# microcontroller.net
KiCad netlist of a schematic drawn in Altium Designer
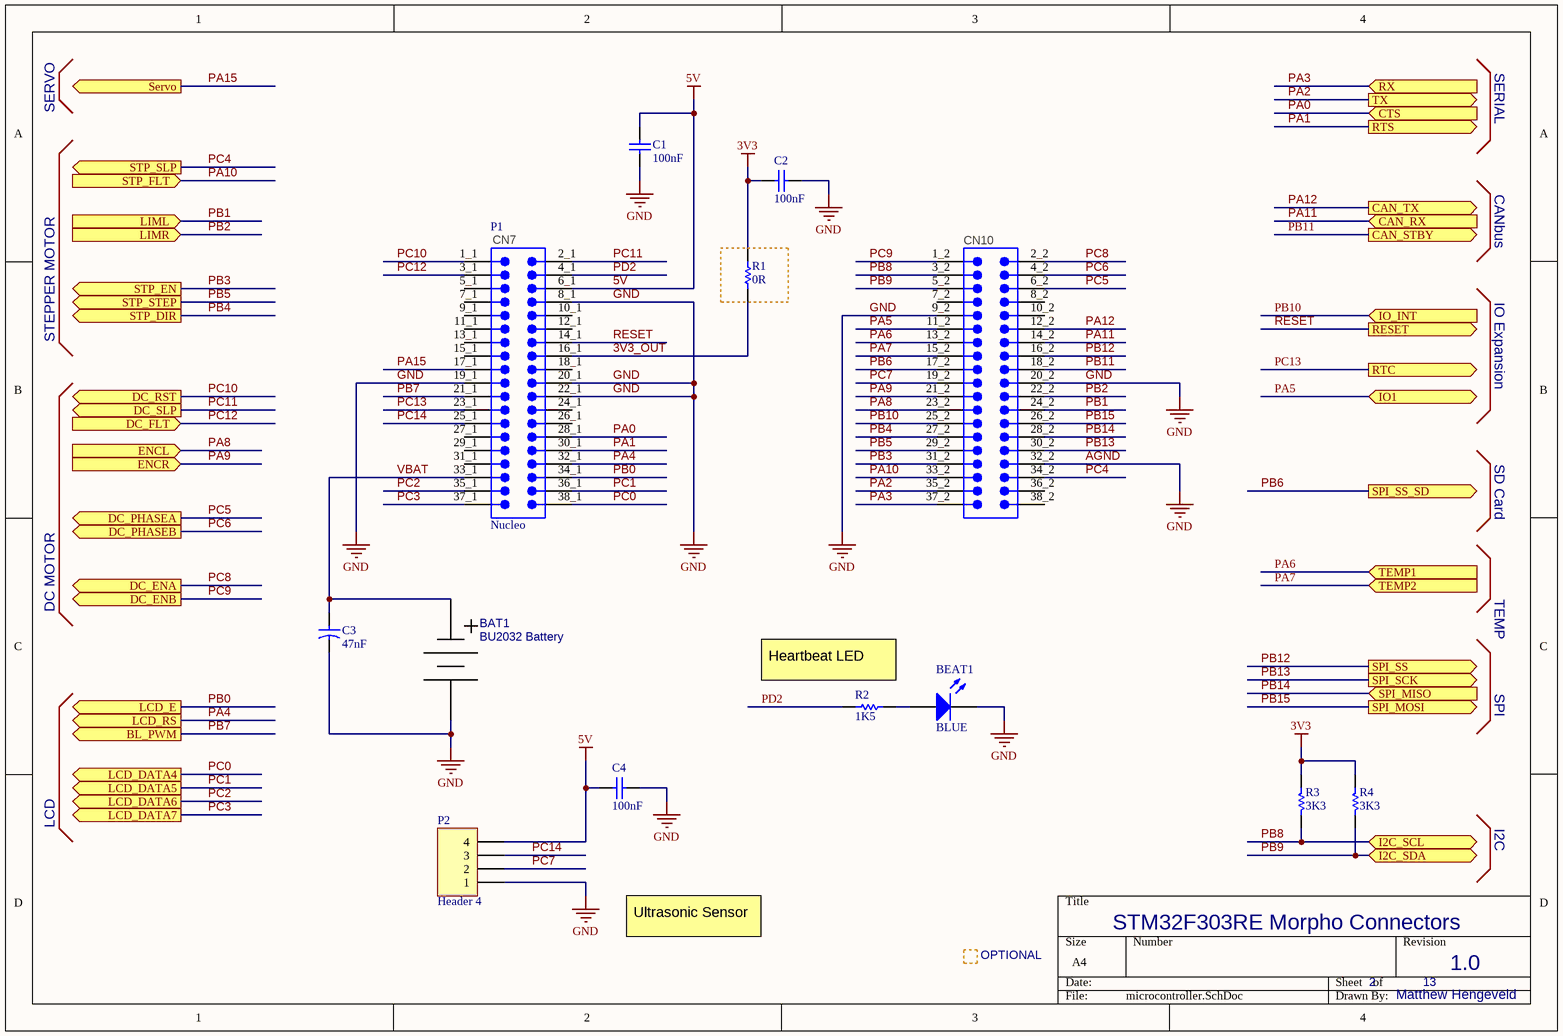
[diagram p0: microcontroller.SchDoc]

(export (version "E")
  (design (tool "Eeschema 10.0.6"))
  (components
    (comp (ref "BAT1")
      (value "BU2032 Battery")
      (footprint "BU2032")
      (libsource (lib "Hengeveld") (part "BU2032 Battery"))
    )
    (comp (ref "BEAT1")
      (value "BLUE")
      (footprint "0805_A")
      (description "SMD mono-color Chip LED, WL-SMCW, Red")
      (fields (field (name "PARTNUMBER") "150080RS75000") (field (name "MANUFACTURER") "Wuerth Elektronik"))
      (libsource (lib "Altium Content Vault") (part "WE-LED_K1A2-2"))
    )
    (comp (ref "C1")
      (value "100nF")
      (footprint "CAPC1608X92X38LL15T08")
      (fields (field (name "PART NUMBER") "VJ0603Y104KNXAO") (field (name "MANUFACTURER") "Vitramon"))
      (libsource (lib "Altium Content Vault") (part "CAP"))
    )
    (comp (ref "C2")
      (value "100nF")
      (footprint "CAPC1608X92X38LL15T08")
      (fields (field (name "PART NUMBER") "VJ0603Y104KNXAO") (field (name "MANUFACTURER") "Vitramon"))
      (libsource (lib "Altium Content Vault") (part "CAP"))
    )
    (comp (ref "C3")
      (value "47nF")
      (footprint "FILM_CAp")
      (fields (field (name "PARTNUMBER") "UUD1V101MNL1GS") (field (name "MANUFACTURER") "Nichicon"))
      (libsource (lib "Hengeveld") (part "CAP-FILM"))
    )
    (comp (ref "C4")
      (value "100nF")
      (footprint "CAPC1608X92X38LL15T08")
      (fields (field (name "PART NUMBER") "VJ0603Y104KNXAO") (field (name "MANUFACTURER") "Vitramon"))
      (libsource (lib "Altium Content Vault") (part "CAP"))
    )
    (comp (ref "P1")
      (value "Nucleo")
      (footprint "NUCLEO")
      (description "STM32F303 Nucleo Development Board")
      (fields (field (name "MANUFACTURER") "Samtec") (field (name "PARTNUMBER") "HW-20-08-F-D-255-090"))
      (libsource (lib "Hengeveld") (part "Nucleo"))
    )
    (comp (ref "P2")
      (value "Header 4")
      (footprint "HDR1X4")
      (description "Header, 4-Pin")
      (fields (field (name "PUBLISHER") "Altium Limited"))
      (libsource (lib "Hengeveld") (part "Header 4"))
    )
    (comp (ref "R1")
      (value "0R")
      (footprint "RESC1608X55X30LL15T15")
      (fields (field (name "MANUFACTURER") "Panasonic") (field (name "PART NUMBER") "ERJ-3GEYJ103V"))
      (libsource (lib "Altium Content Vault") (part "RES"))
    )
    (comp (ref "R2")
      (value "1K5")
      (footprint "RESC1608X55X30LL15T15")
      (fields (field (name "MANUFACTURER") "Panasonic") (field (name "PART NUMBER") "ERJ-3GEYJ103V"))
      (libsource (lib "Altium Content Vault") (part "RES"))
    )
    (comp (ref "R3")
      (value "3K3")
      (footprint "RESC1608X55X30LL15T15")
      (fields (field (name "MANUFACTURER") "Panasonic") (field (name "PART NUMBER") "ERJ-3GEYJ103V"))
      (libsource (lib "Altium Content Vault") (part "RES"))
    )
    (comp (ref "R4")
      (value "3K3")
      (footprint "RESC1608X55X30LL15T15")
      (fields (field (name "MANUFACTURER") "Panasonic") (field (name "PART NUMBER") "ERJ-3GEYJ103V"))
      (libsource (lib "Altium Content Vault") (part "RES"))
    )
  )
  (nets
    (net (code "1") (name "/3V3_OUT") (class "Default")
      (node (ref "P1") (pin "16_1") (pinfunction "16_16_1") (pintype "passive"))
      (node (ref "R1") (pin "1") (pinfunction "1_1") (pintype "passive"))
    )
    (net (code "3") (name "/PA0") (class "Default")
      (node (ref "P1") (pin "28_1") (pinfunction "28_28_1") (pintype "passive"))
    )
    (net (code "4") (name "/PA1") (class "Default")
      (node (ref "P1") (pin "30_1") (pinfunction "30_30_1") (pintype "passive"))
    )
    (net (code "5") (name "/PA2") (class "Default")
      (node (ref "P1") (pin "35_2") (pinfunction "35_35_2") (pintype "passive"))
    )
    (net (code "6") (name "/PA3") (class "Default")
      (node (ref "P1") (pin "37_2") (pinfunction "37_37_2") (pintype "passive"))
    )
    (net (code "7") (name "/PA4") (class "Default")
      (node (ref "P1") (pin "32_1") (pinfunction "32_32_1") (pintype "passive"))
    )
    (net (code "8") (name "/PA5") (class "Default")
      (node (ref "P1") (pin "11_2") (pinfunction "11_11_2") (pintype "passive"))
    )
    (net (code "9") (name "/PA6") (class "Default")
      (node (ref "P1") (pin "13_2") (pinfunction "13_13_2") (pintype "passive"))
    )
    (net (code "10") (name "/PA7") (class "Default")
      (node (ref "P1") (pin "15_2") (pinfunction "15_15_2") (pintype "passive"))
    )
    (net (code "11") (name "/PA8") (class "Default")
      (node (ref "P1") (pin "23_2") (pinfunction "23_23_2") (pintype "passive"))
    )
    (net (code "12") (name "/PA9") (class "Default")
      (node (ref "P1") (pin "21_2") (pinfunction "21_21_2") (pintype "passive"))
    )
    (net (code "13") (name "/PA10") (class "Default")
      (node (ref "P1") (pin "33_2") (pinfunction "33_33_2") (pintype "passive"))
    )
    (net (code "14") (name "/PA11") (class "Default")
      (node (ref "P1") (pin "14_2") (pinfunction "14_14_2") (pintype "passive"))
    )
    (net (code "15") (name "/PA12") (class "Default")
      (node (ref "P1") (pin "12_2") (pinfunction "12_12_2") (pintype "passive"))
    )
    (net (code "16") (name "/PA15") (class "Default")
      (node (ref "P1") (pin "17_1") (pinfunction "17_17_1") (pintype "passive"))
    )
    (net (code "17") (name "/PB0") (class "Default")
      (node (ref "P1") (pin "34_1") (pinfunction "34_34_1") (pintype "passive"))
    )
    (net (code "18") (name "/PB1") (class "Default")
      (node (ref "P1") (pin "24_2") (pinfunction "24_24_2") (pintype "passive"))
    )
    (net (code "19") (name "/PB2") (class "Default")
      (node (ref "P1") (pin "22_2") (pinfunction "22_22_2") (pintype "passive"))
    )
    (net (code "20") (name "/PB3") (class "Default")
      (node (ref "P1") (pin "31_2") (pinfunction "31_31_2") (pintype "passive"))
    )
    (net (code "21") (name "/PB4") (class "Default")
      (node (ref "P1") (pin "27_2") (pinfunction "27_27_2") (pintype "passive"))
    )
    (net (code "22") (name "/PB5") (class "Default")
      (node (ref "P1") (pin "29_2") (pinfunction "29_29_2") (pintype "passive"))
    )
    (net (code "23") (name "/PB6") (class "Default")
      (node (ref "P1") (pin "17_2") (pinfunction "17_17_2") (pintype "passive"))
    )
    (net (code "24") (name "/PB7") (class "Default")
      (node (ref "P1") (pin "21_1") (pinfunction "21_21_1") (pintype "passive"))
    )
    (net (code "25") (name "/PB8") (class "Default")
      (node (ref "P1") (pin "3_2") (pinfunction "3_3_2") (pintype "passive"))
      (node (ref "R3") (pin "2") (pinfunction "2_2") (pintype "passive"))
    )
    (net (code "26") (name "/PB9") (class "Default")
      (node (ref "P1") (pin "5_2") (pinfunction "5_5_2") (pintype "passive"))
      (node (ref "R4") (pin "2") (pinfunction "2_2") (pintype "passive"))
    )
    (net (code "27") (name "/PB10") (class "Default")
      (node (ref "P1") (pin "25_2") (pinfunction "25_25_2") (pintype "passive"))
    )
    (net (code "28") (name "/PB11") (class "Default")
      (node (ref "P1") (pin "18_2") (pinfunction "18_18_2") (pintype "passive"))
    )
    (net (code "29") (name "/PB12") (class "Default")
      (node (ref "P1") (pin "16_2") (pinfunction "16_16_2") (pintype "passive"))
    )
    (net (code "30") (name "/PB13") (class "Default")
      (node (ref "P1") (pin "30_2") (pinfunction "30_30_2") (pintype "passive"))
    )
    (net (code "31") (name "/PB14") (class "Default")
      (node (ref "P1") (pin "28_2") (pinfunction "28_28_2") (pintype "passive"))
    )
    (net (code "32") (name "/PB15") (class "Default")
      (node (ref "P1") (pin "26_2") (pinfunction "26_26_2") (pintype "passive"))
    )
    (net (code "33") (name "/PC0") (class "Default")
      (node (ref "P1") (pin "38_1") (pinfunction "38_38_1") (pintype "passive"))
    )
    (net (code "34") (name "/PC1") (class "Default")
      (node (ref "P1") (pin "36_1") (pinfunction "36_36_1") (pintype "passive"))
    )
    (net (code "35") (name "/PC2") (class "Default")
      (node (ref "P1") (pin "35_1") (pinfunction "35_35_1") (pintype "passive"))
    )
    (net (code "36") (name "/PC3") (class "Default")
      (node (ref "P1") (pin "37_1") (pinfunction "37_37_1") (pintype "passive"))
    )
    (net (code "37") (name "/PC4") (class "Default")
      (node (ref "P1") (pin "34_2") (pinfunction "34_34_2") (pintype "passive"))
    )
    (net (code "38") (name "/PC5") (class "Default")
      (node (ref "P1") (pin "6_2") (pinfunction "6_6_2") (pintype "passive"))
    )
    (net (code "39") (name "/PC6") (class "Default")
      (node (ref "P1") (pin "4_2") (pinfunction "4_4_2") (pintype "passive"))
    )
    (net (code "40") (name "/PC7") (class "Default")
      (node (ref "P1") (pin "19_2") (pinfunction "19_19_2") (pintype "passive"))
      (node (ref "P2") (pin "2") (pinfunction "2_2") (pintype "passive"))
    )
    (net (code "41") (name "/PC8") (class "Default")
      (node (ref "P1") (pin "2_2") (pinfunction "2_2_2") (pintype "passive"))
    )
    (net (code "42") (name "/PC9") (class "Default")
      (node (ref "P1") (pin "1_2") (pinfunction "1_1_2") (pintype "passive"))
    )
    (net (code "43") (name "/PC10") (class "Default")
      (node (ref "P1") (pin "1_1") (pinfunction "1_1_1") (pintype "passive"))
    )
    (net (code "44") (name "/PC11") (class "Default")
      (node (ref "P1") (pin "2_1") (pinfunction "2_2_1") (pintype "passive"))
    )
    (net (code "45") (name "/PC12") (class "Default")
      (node (ref "P1") (pin "3_1") (pinfunction "3_3_1") (pintype "passive"))
    )
    (net (code "46") (name "/PC13") (class "Default")
      (node (ref "P1") (pin "23_1") (pinfunction "23_23_1") (pintype "passive"))
    )
    (net (code "47") (name "/PC14") (class "Default")
      (node (ref "P1") (pin "25_1") (pinfunction "25_25_1") (pintype "passive"))
      (node (ref "P2") (pin "3") (pinfunction "3_3") (pintype "passive"))
    )
    (net (code "48") (name "/PD2") (class "Default")
      (node (ref "P1") (pin "4_1") (pinfunction "4_4_1") (pintype "passive"))
      (node (ref "R2") (pin "1") (pinfunction "1_1") (pintype "passive"))
    )
    (net (code "49") (name "/RESET") (class "Default")
      (node (ref "P1") (pin "14_1") (pinfunction "14_14_1") (pintype "passive"))
    )
    (net (code "50") (name "/VBAT") (class "Default")
      (node (ref "BAT1") (pin "+") (pinfunction "+_+") (pintype "power_in"))
      (node (ref "C3") (pin "1") (pinfunction "1_1") (pintype "passive"))
      (node (ref "P1") (pin "33_1") (pinfunction "33_33_1") (pintype "passive"))
    )
    (net (code "51") (name "3V3") (class "Default")
      (node (ref "C2") (pin "2") (pinfunction "2_2") (pintype "passive"))
      (node (ref "R1") (pin "2") (pinfunction "2_2") (pintype "passive"))
      (node (ref "R3") (pin "1") (pinfunction "1_1") (pintype "passive"))
      (node (ref "R4") (pin "1") (pinfunction "1_1") (pintype "passive"))
    )
    (net (code "52") (name "5V") (class "Default")
      (node (ref "C1") (pin "2") (pinfunction "2_2") (pintype "passive"))
      (node (ref "C4") (pin "2") (pinfunction "2_2") (pintype "passive"))
      (node (ref "P1") (pin "6_1") (pinfunction "6_6_1") (pintype "passive"))
      (node (ref "P2") (pin "4") (pinfunction "4_4") (pintype "passive"))
    )
    (net (code "53") (name "GND") (class "Default")
      (node (ref "BAT1") (pin "-") (pinfunction "-_-") (pintype "power_in"))
      (node (ref "BEAT1") (pin "1") (pinfunction "K_1") (pintype "passive"))
      (node (ref "C1") (pin "1") (pinfunction "1_1") (pintype "passive"))
      (node (ref "C2") (pin "1") (pinfunction "1_1") (pintype "passive"))
      (node (ref "C3") (pin "2") (pinfunction "2_2") (pintype "passive"))
      (node (ref "C4") (pin "1") (pinfunction "1_1") (pintype "passive"))
      (node (ref "P1") (pin "19_1") (pinfunction "19_19_1") (pintype "passive"))
      (node (ref "P1") (pin "20_1") (pinfunction "20_20_1") (pintype "passive"))
      (node (ref "P1") (pin "20_2") (pinfunction "20_20_2") (pintype "passive"))
      (node (ref "P1") (pin "22_1") (pinfunction "22_22_1") (pintype "passive"))
      (node (ref "P1") (pin "32_2") (pinfunction "32_32_2") (pintype "passive"))
      (node (ref "P1") (pin "8_1") (pinfunction "8_8_1") (pintype "passive"))
      (node (ref "P1") (pin "9_2") (pinfunction "9_9_2") (pintype "passive"))
      (node (ref "P2") (pin "1") (pinfunction "1_1") (pintype "passive"))
    )
    (net (code "54") (name "Net-(BEAT1-A)") (class "Default")
      (node (ref "BEAT1") (pin "2") (pinfunction "A_2") (pintype "passive"))
      (node (ref "R2") (pin "2") (pinfunction "2_2") (pintype "passive"))
    )
    (net (code "55") (name "unconnected-(P1-5-Pad5_1)") (class "Default")
      (node (ref "P1") (pin "5_1") (pinfunction "5_5_1") (pintype "passive"))
    )
    (net (code "56") (name "unconnected-(P1-7-Pad7_1)") (class "Default")
      (node (ref "P1") (pin "7_1") (pinfunction "7_7_1") (pintype "passive"))
    )
    (net (code "57") (name "unconnected-(P1-7-Pad7_2)") (class "Default")
      (node (ref "P1") (pin "7_2") (pinfunction "7_7_2") (pintype "passive"))
    )
    (net (code "58") (name "unconnected-(P1-8-Pad8_2)") (class "Default")
      (node (ref "P1") (pin "8_2") (pinfunction "8_8_2") (pintype "passive"))
    )
    (net (code "59") (name "unconnected-(P1-9-Pad9_1)") (class "Default")
      (node (ref "P1") (pin "9_1") (pinfunction "9_9_1") (pintype "passive"))
    )
    (net (code "60") (name "unconnected-(P1-10-Pad10_1)") (class "Default")
      (node (ref "P1") (pin "10_1") (pinfunction "10_10_1") (pintype "passive"))
    )
    (net (code "61") (name "unconnected-(P1-10-Pad10_2)") (class "Default")
      (node (ref "P1") (pin "10_2") (pinfunction "10_10_2") (pintype "passive"))
    )
    (net (code "62") (name "unconnected-(P1-11-Pad11_1)") (class "Default")
      (node (ref "P1") (pin "11_1") (pinfunction "11_11_1") (pintype "passive"))
    )
    (net (code "63") (name "unconnected-(P1-12-Pad12_1)") (class "Default")
      (node (ref "P1") (pin "12_1") (pinfunction "12_12_1") (pintype "passive"))
    )
    (net (code "64") (name "unconnected-(P1-13-Pad13_1)") (class "Default")
      (node (ref "P1") (pin "13_1") (pinfunction "13_13_1") (pintype "passive"))
    )
    (net (code "65") (name "unconnected-(P1-15-Pad15_1)") (class "Default")
      (node (ref "P1") (pin "15_1") (pinfunction "15_15_1") (pintype "passive"))
    )
    (net (code "66") (name "unconnected-(P1-18-Pad18_1)") (class "Default")
      (node (ref "P1") (pin "18_1") (pinfunction "18_18_1") (pintype "passive"))
    )
    (net (code "67") (name "unconnected-(P1-24-Pad24_1)") (class "Default")
      (node (ref "P1") (pin "24_1") (pinfunction "24_24_1") (pintype "passive"))
    )
    (net (code "68") (name "unconnected-(P1-26-Pad26_1)") (class "Default")
      (node (ref "P1") (pin "26_1") (pinfunction "26_26_1") (pintype "passive"))
    )
    (net (code "69") (name "unconnected-(P1-27-Pad27_1)") (class "Default")
      (node (ref "P1") (pin "27_1") (pinfunction "27_27_1") (pintype "passive"))
    )
    (net (code "70") (name "unconnected-(P1-29-Pad29_1)") (class "Default")
      (node (ref "P1") (pin "29_1") (pinfunction "29_29_1") (pintype "passive"))
    )
    (net (code "71") (name "unconnected-(P1-31-Pad31_1)") (class "Default")
      (node (ref "P1") (pin "31_1") (pinfunction "31_31_1") (pintype "passive"))
    )
    (net (code "72") (name "unconnected-(P1-36-Pad36_2)") (class "Default")
      (node (ref "P1") (pin "36_2") (pinfunction "36_36_2") (pintype "passive"))
    )
    (net (code "73") (name "unconnected-(P1-38-Pad38_2)") (class "Default")
      (node (ref "P1") (pin "38_2") (pinfunction "38_38_2") (pintype "passive"))
    )
  )
)
